# ElectroMechanical_Control.net
KiCad netlist of a schematic drawn in Altium Designer
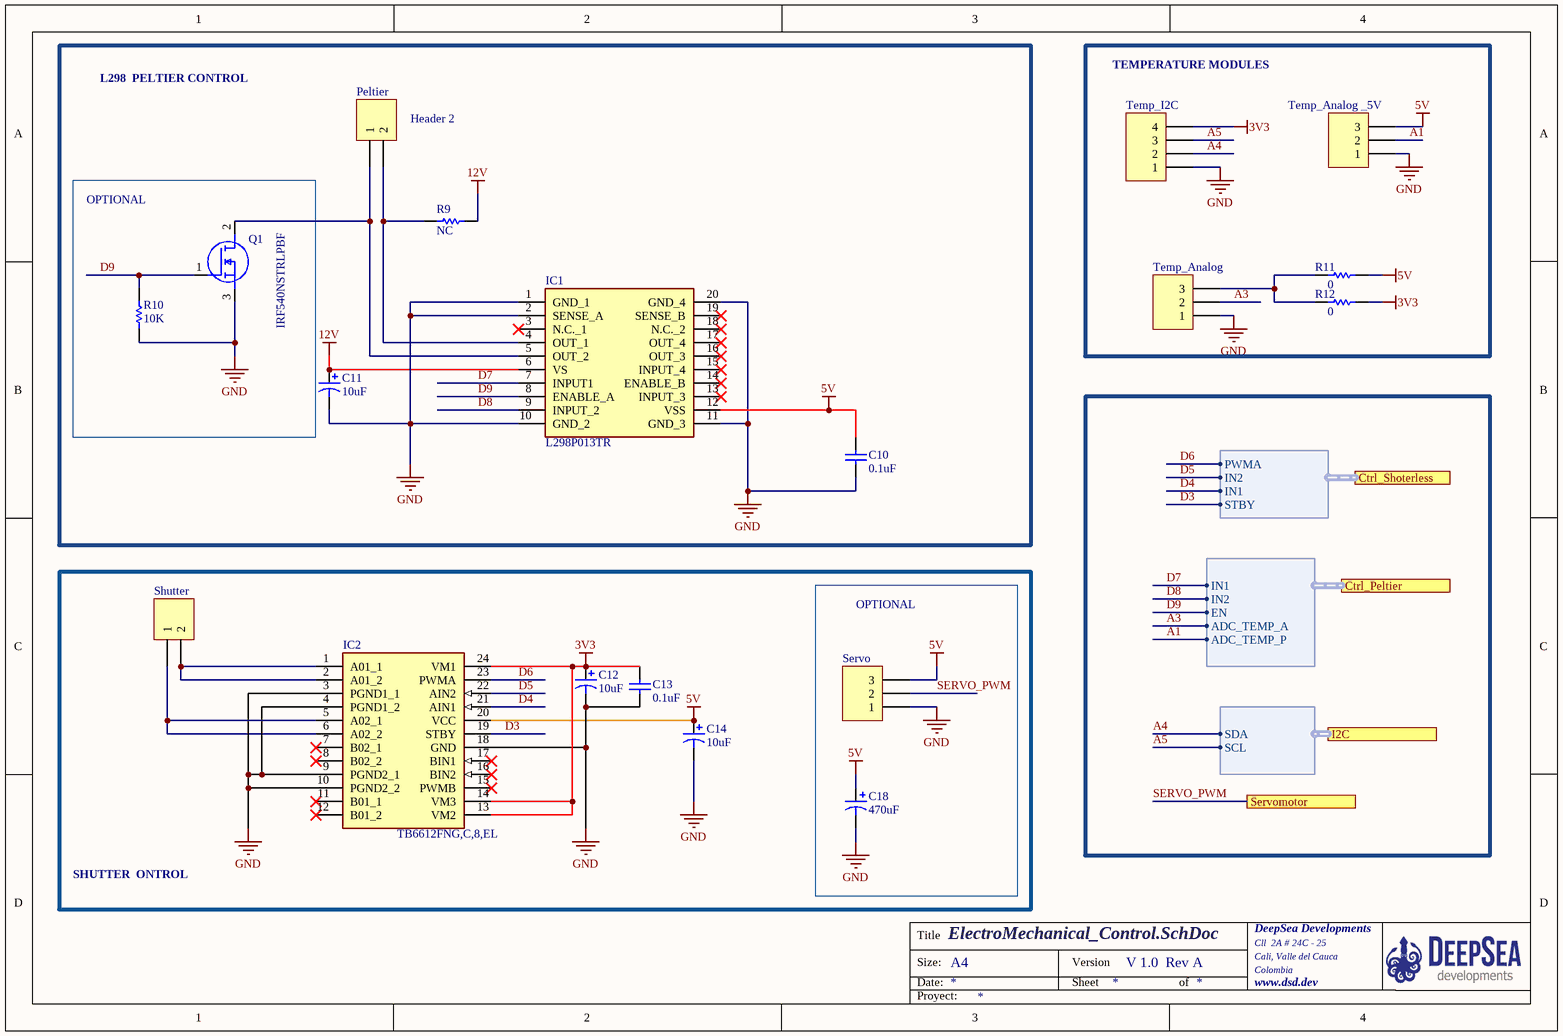
[diagram p0: ElectroMechanical_Control.SchDoc]

(export (version "E")
  (design (tool "Eeschema 10.0.6"))
  (components
    (comp (ref "C10") (value "0.1uF") (footprint "C0603_L") (libsource (lib "General") (part "C_SMD")))
    (comp (ref "C11")
      (value "10uF")
      (footprint "C_TANT_A_3216_L")
      (libsource (lib "General") (part "CP_SMD"))
    )
    (comp (ref "C12")
      (value "10uF")
      (footprint "C_TANT_A_3216_L")
      (libsource (lib "General") (part "CP_SMD"))
    )
    (comp (ref "C13") (value "0.1uF") (footprint "C0603_L") (libsource (lib "General") (part "C_SMD")))
    (comp (ref "C14")
      (value "10uF")
      (footprint "C_TANT_A_3216_L")
      (libsource (lib "General") (part "CP_SMD"))
    )
    (comp (ref "C18")
      (value "470uF")
      (footprint "C_ELECT_8X10_SMD_L")
      (description "CAP ALUM 470UF 20% 10V SMD")
      (fields
        (field (name "MANUFACTURER") "Nichicon")
        (field (name "MANUFACTURER PART NUMBER") "UWT1A471MNL1GS")
      )
      (libsource (lib "General") (part "C_SMD_UWT1A471MNL1GS"))
    )
    (comp (ref "IC1")
      (value "L298P013TR")
      (footprint "SamacSys:SOIC127P1420X360-20N")
      (description "Integrated Circuit")
      (fields (field (name "MOUSER PART NUMBER") "511-L298P-TR") (field (name "RS PART NUMBER") "8805308P"))
      (libsource (lib "*") (part "L298P013TR"))
    )
    (comp (ref "IC2")
      (value "TB6612FNG,C,8,EL")
      (footprint "SamacSys:SOP65P760X160-24N")
      (description "Integrated Circuit")
      (fields (field (name "MOUSER PART NUMBER") "757-TB6612FNGC8EL"))
      (libsource (lib "*") (part "TB6612FNG,C,8,EL"))
    )
    (comp (ref "Peltier")
      (value "Header 2")
      (footprint "HDR1X2")
      (description "Header, 2-Pin")
      (fields (field (name "PUBLISHER") "Altium Limited"))
      (libsource (lib "Miscellaneous Connectors") (part "Header 2"))
    )
    (comp (ref "Q1")
      (value "IRF540NSTRLPBF")
      (footprint "SamacSys:D2PAK")
      (description "MOSFET (N-Channel)")
      (fields (field (name "MOUSER PART NUMBER") "942-IRF540NSTRLPBF"))
      (libsource (lib "*") (part "IRF540NSTRLPBF"))
    )
    (comp (ref "R9") (value "NC") (footprint "R0805_M") (libsource (lib "General") (part "R_SMD")))
    (comp (ref "R10") (value "10K") (footprint "R0603_L") (libsource (lib "General") (part "R_SMD")))
    (comp (ref "R11") (value "0") (footprint "R0603_L") (libsource (lib "General") (part "R_SMD")))
    (comp (ref "R12") (value "0") (footprint "R0603_L") (libsource (lib "General") (part "R_SMD")))
    (comp (ref "Servo")
      (value "Temp_Analog")
      (footprint "HDR1X3")
      (description "Header, 3-Pin")
      (fields (field (name "PUBLISHER") "Altium Limited"))
      (libsource (lib "Miscellaneous Connectors") (part "Header 3"))
    )
    (comp (ref "Shutter")
      (value "Shotter")
      (footprint "HDR1X2")
      (description "Header, 2-Pin")
      (fields (field (name "PUBLISHER") "Altium Limited"))
      (libsource (lib "Miscellaneous Connectors") (part "Header 2"))
    )
    (comp (ref "Temp_Analog")
      (value "Temp_Analog")
      (footprint "HDR1X3")
      (description "Header, 3-Pin")
      (fields (field (name "PUBLISHER") "Altium Limited"))
      (libsource (lib "Miscellaneous Connectors") (part "Header 3"))
    )
    (comp (ref "Temp_Analog _5V")
      (value "Temp_Analog _5V")
      (footprint "HDR1X3")
      (description "Header, 3-Pin")
      (fields (field (name "PUBLISHER") "Altium Limited"))
      (libsource (lib "Miscellaneous Connectors") (part "Header 3"))
    )
    (comp (ref "Temp_I2C")
      (value "Temp_I2C")
      (footprint "HDR1X4")
      (description "Header, 4-Pin")
      (fields (field (name "PUBLISHER") "Altium Limited"))
      (libsource (lib "Miscellaneous Connectors") (part "Header 4"))
    )
  )
  (nets
    (net (code "4") (name "/A1") (class "Default")
      (node (ref "Temp_Analog _5V") (pin "2") (pinfunction "2_2") (pintype "passive"))
    )
    (net (code "5") (name "/A3") (class "Default")
      (node (ref "Temp_Analog") (pin "2") (pinfunction "2_2") (pintype "passive"))
    )
    (net (code "6") (name "/A4") (class "Default")
      (node (ref "Temp_I2C") (pin "2") (pinfunction "2_2") (pintype "passive"))
    )
    (net (code "7") (name "/A5") (class "Default")
      (node (ref "Temp_I2C") (pin "3") (pinfunction "3_3") (pintype "passive"))
    )
    (net (code "8") (name "/D3") (class "Default")
      (node (ref "IC2") (pin "19") (pinfunction "STBY_19") (pintype "passive"))
    )
    (net (code "9") (name "/D4") (class "Default")
      (node (ref "IC2") (pin "21") (pinfunction "AIN1_21") (pintype "input"))
    )
    (net (code "10") (name "/D5") (class "Default")
      (node (ref "IC2") (pin "22") (pinfunction "AIN2_22") (pintype "input"))
    )
    (net (code "11") (name "/D6") (class "Default")
      (node (ref "IC2") (pin "23") (pinfunction "PWMA_23") (pintype "passive"))
    )
    (net (code "12") (name "/D7") (class "Default")
      (node (ref "IC1") (pin "7") (pinfunction "INPUT1_7") (pintype "passive"))
    )
    (net (code "13") (name "/D8") (class "Default")
      (node (ref "IC1") (pin "9") (pinfunction "INPUT_2_9") (pintype "passive"))
    )
    (net (code "14") (name "/D9") (class "Default")
      (node (ref "IC1") (pin "8") (pinfunction "ENABLE_A_8") (pintype "passive"))
      (node (ref "Q1") (pin "1") (pinfunction "G_1") (pintype "passive"))
      (node (ref "R10") (pin "2") (pinfunction "2_2") (pintype "passive"))
    )
    (net (code "15") (name "/SERVO_PWM") (class "Default")
      (node (ref "Servo") (pin "2") (pinfunction "2_2") (pintype "passive"))
    )
    (net (code "19") (name "3V3") (class "Default")
      (node (ref "C12") (pin "1") (pinfunction "1_1") (pintype "passive"))
      (node (ref "C13") (pin "2") (pinfunction "2_2") (pintype "passive"))
      (node (ref "IC2") (pin "13") (pinfunction "VM2_13") (pintype "passive"))
      (node (ref "IC2") (pin "14") (pinfunction "VM3_14") (pintype "passive"))
      (node (ref "IC2") (pin "24") (pinfunction "VM1_24") (pintype "passive"))
      (node (ref "R12") (pin "2") (pinfunction "2_2") (pintype "passive"))
      (node (ref "Temp_I2C") (pin "4") (pinfunction "4_4") (pintype "passive"))
    )
    (net (code "20") (name "5V") (class "Default")
      (node (ref "C10") (pin "2") (pinfunction "2_2") (pintype "passive"))
      (node (ref "C14") (pin "1") (pinfunction "1_1") (pintype "passive"))
      (node (ref "C18") (pin "1") (pinfunction "1_1") (pintype "passive"))
      (node (ref "IC1") (pin "12") (pinfunction "VSS_12") (pintype "passive"))
      (node (ref "IC2") (pin "20") (pinfunction "VCC_20") (pintype "power_in"))
      (node (ref "R11") (pin "2") (pinfunction "2_2") (pintype "passive"))
      (node (ref "Servo") (pin "3") (pinfunction "3_3") (pintype "passive"))
      (node (ref "Temp_Analog _5V") (pin "3") (pinfunction "3_3") (pintype "passive"))
    )
    (net (code "21") (name "12V") (class "Default")
      (node (ref "C11") (pin "1") (pinfunction "1_1") (pintype "passive"))
      (node (ref "IC1") (pin "6") (pinfunction "VS_6") (pintype "passive"))
      (node (ref "R9") (pin "2") (pinfunction "2_2") (pintype "passive"))
    )
    (net (code "22") (name "GND") (class "Default")
      (node (ref "C10") (pin "1") (pinfunction "1_1") (pintype "passive"))
      (node (ref "C11") (pin "2") (pinfunction "2_2") (pintype "passive"))
      (node (ref "C12") (pin "2") (pinfunction "2_2") (pintype "passive"))
      (node (ref "C13") (pin "1") (pinfunction "1_1") (pintype "passive"))
      (node (ref "C14") (pin "2") (pinfunction "2_2") (pintype "passive"))
      (node (ref "C18") (pin "2") (pinfunction "2_2") (pintype "passive"))
      (node (ref "IC1") (pin "1") (pinfunction "GND_1_1") (pintype "passive"))
      (node (ref "IC1") (pin "10") (pinfunction "GND_2_10") (pintype "passive"))
      (node (ref "IC1") (pin "11") (pinfunction "GND_3_11") (pintype "passive"))
      (node (ref "IC1") (pin "2") (pinfunction "SENSE_A_2") (pintype "passive"))
      (node (ref "IC1") (pin "20") (pinfunction "GND_4_20") (pintype "passive"))
      (node (ref "IC2") (pin "10") (pinfunction "PGND2_2_10") (pintype "power_in"))
      (node (ref "IC2") (pin "18") (pinfunction "GND_18") (pintype "power_in"))
      (node (ref "IC2") (pin "3") (pinfunction "PGND1_1_3") (pintype "power_in"))
      (node (ref "IC2") (pin "4") (pinfunction "PGND1_2_4") (pintype "power_in"))
      (node (ref "IC2") (pin "9") (pinfunction "PGND2_1_9") (pintype "power_in"))
      (node (ref "Q1") (pin "3") (pinfunction "S_3") (pintype "passive"))
      (node (ref "R10") (pin "1") (pinfunction "1_1") (pintype "passive"))
      (node (ref "Servo") (pin "1") (pinfunction "1_1") (pintype "passive"))
      (node (ref "Temp_Analog") (pin "1") (pinfunction "1_1") (pintype "passive"))
      (node (ref "Temp_Analog _5V") (pin "1") (pinfunction "1_1") (pintype "passive"))
      (node (ref "Temp_I2C") (pin "1") (pinfunction "1_1") (pintype "passive"))
    )
    (net (code "23") (name "Net-(IC1-OUT_1)") (class "Default")
      (node (ref "IC1") (pin "4") (pinfunction "OUT_1_4") (pintype "passive"))
      (node (ref "Peltier") (pin "2") (pinfunction "2_2") (pintype "passive"))
      (node (ref "R9") (pin "1") (pinfunction "1_1") (pintype "passive"))
    )
    (net (code "24") (name "Net-(IC1-OUT_2)") (class "Default")
      (node (ref "IC1") (pin "5") (pinfunction "OUT_2_5") (pintype "passive"))
      (node (ref "Peltier") (pin "1") (pinfunction "1_1") (pintype "passive"))
      (node (ref "Q1") (pin "2") (pinfunction "D_2") (pintype "passive"))
    )
    (net (code "25") (name "Net-(IC2-A01_1)") (class "Default")
      (node (ref "IC2") (pin "1") (pinfunction "A01_1_1") (pintype "passive"))
      (node (ref "IC2") (pin "2") (pinfunction "A01_2_2") (pintype "passive"))
      (node (ref "Shutter") (pin "2") (pinfunction "2_2") (pintype "passive"))
    )
    (net (code "26") (name "Net-(IC2-A02_1)") (class "Default")
      (node (ref "IC2") (pin "5") (pinfunction "A02_1_5") (pintype "passive"))
      (node (ref "IC2") (pin "6") (pinfunction "A02_2_6") (pintype "passive"))
      (node (ref "Shutter") (pin "1") (pinfunction "1_1") (pintype "passive"))
    )
    (net (code "27") (name "Net-(R11-Pad1)") (class "Default")
      (node (ref "R11") (pin "1") (pinfunction "1_1") (pintype "passive"))
      (node (ref "R12") (pin "1") (pinfunction "1_1") (pintype "passive"))
      (node (ref "Temp_Analog") (pin "3") (pinfunction "3_3") (pintype "passive"))
    )
    (net (code "28") (name "unconnected-(IC1-ENABLE_B-Pad14)") (class "Default")
      (node (ref "IC1") (pin "14") (pinfunction "ENABLE_B_14") (pintype "passive+no_connect"))
    )
    (net (code "29") (name "unconnected-(IC1-INPUT_3-Pad13)") (class "Default")
      (node (ref "IC1") (pin "13") (pinfunction "INPUT_3_13") (pintype "passive+no_connect"))
    )
    (net (code "30") (name "unconnected-(IC1-INPUT_4-Pad15)") (class "Default")
      (node (ref "IC1") (pin "15") (pinfunction "INPUT_4_15") (pintype "passive+no_connect"))
    )
    (net (code "31") (name "unconnected-(IC1-N.C._1-Pad3)") (class "Default")
      (node (ref "IC1") (pin "3") (pinfunction "N.C._1_3") (pintype "passive+no_connect"))
    )
    (net (code "32") (name "unconnected-(IC1-N.C._2-Pad18)") (class "Default")
      (node (ref "IC1") (pin "18") (pinfunction "N.C._2_18") (pintype "passive+no_connect"))
    )
    (net (code "33") (name "unconnected-(IC1-OUT_3-Pad16)") (class "Default")
      (node (ref "IC1") (pin "16") (pinfunction "OUT_3_16") (pintype "passive+no_connect"))
    )
    (net (code "34") (name "unconnected-(IC1-OUT_4-Pad17)") (class "Default")
      (node (ref "IC1") (pin "17") (pinfunction "OUT_4_17") (pintype "passive+no_connect"))
    )
    (net (code "35") (name "unconnected-(IC1-SENSE_B-Pad19)") (class "Default")
      (node (ref "IC1") (pin "19") (pinfunction "SENSE_B_19") (pintype "passive+no_connect"))
    )
    (net (code "36") (name "unconnected-(IC2-B01_1-Pad11)") (class "Default")
      (node (ref "IC2") (pin "11") (pinfunction "B01_1_11") (pintype "passive+no_connect"))
    )
    (net (code "37") (name "unconnected-(IC2-B01_2-Pad12)") (class "Default")
      (node (ref "IC2") (pin "12") (pinfunction "B01_2_12") (pintype "passive+no_connect"))
    )
    (net (code "38") (name "unconnected-(IC2-B02_1-Pad7)") (class "Default")
      (node (ref "IC2") (pin "7") (pinfunction "B02_1_7") (pintype "passive+no_connect"))
    )
    (net (code "39") (name "unconnected-(IC2-B02_2-Pad8)") (class "Default")
      (node (ref "IC2") (pin "8") (pinfunction "B02_2_8") (pintype "passive+no_connect"))
    )
    (net (code "40") (name "unconnected-(IC2-BIN1-Pad17)") (class "Default")
      (node (ref "IC2") (pin "17") (pinfunction "BIN1_17") (pintype "input+no_connect"))
    )
    (net (code "41") (name "unconnected-(IC2-BIN2-Pad16)") (class "Default")
      (node (ref "IC2") (pin "16") (pinfunction "BIN2_16") (pintype "input+no_connect"))
    )
    (net (code "42") (name "unconnected-(IC2-PWMB-Pad15)") (class "Default")
      (node (ref "IC2") (pin "15") (pinfunction "PWMB_15") (pintype "passive+no_connect"))
    )
  )
)
